# motor_control.net
KiCad netlist of a schematic drawn in Altium Designer
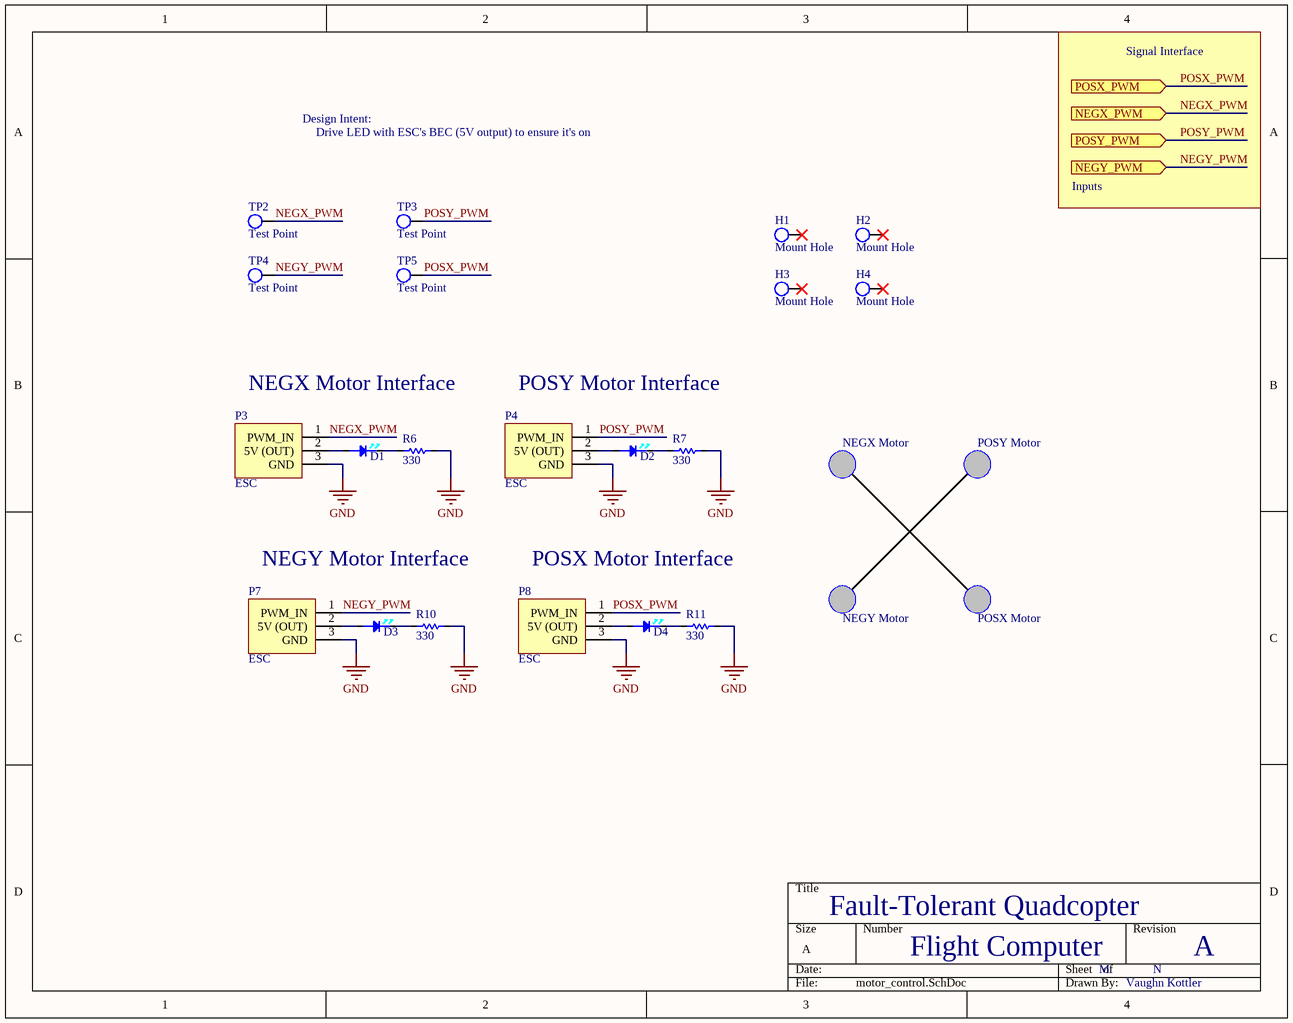
[diagram p0: motor_control.SchDoc]

(export (version "E")
  (design (tool "Eeschema 10.0.6"))
  (components
    (comp (ref "D1")
      (value "LED-WHT-20mA")
      (footprint "LED-0805")
      (description "2.2V, 0805")
      (libsource (lib "passive") (part "LED-WHT-20mA"))
    )
    (comp (ref "D2")
      (value "LED-WHT-20mA")
      (footprint "LED-0805")
      (description "2.2V, 0805")
      (libsource (lib "passive") (part "LED-WHT-20mA"))
    )
    (comp (ref "D3")
      (value "LED-WHT-20mA")
      (footprint "LED-0805")
      (description "2.2V, 0805")
      (libsource (lib "passive") (part "LED-WHT-20mA"))
    )
    (comp (ref "D4")
      (value "LED-WHT-20mA")
      (footprint "LED-0805")
      (description "2.2V, 0805")
      (libsource (lib "passive") (part "LED-WHT-20mA"))
    )
    (comp (ref "H1")
      (value "Mount Hole")
      (footprint "4mm Mount Hole")
      (libsource (lib "connector") (part "Mount Hole"))
    )
    (comp (ref "H2")
      (value "Mount Hole")
      (footprint "4mm Mount Hole")
      (libsource (lib "connector") (part "Mount Hole"))
    )
    (comp (ref "H3")
      (value "Mount Hole")
      (footprint "4mm Mount Hole")
      (libsource (lib "connector") (part "Mount Hole"))
    )
    (comp (ref "H4")
      (value "Mount Hole")
      (footprint "4mm Mount Hole")
      (libsource (lib "connector") (part "Mount Hole"))
    )
    (comp (ref "P3")
      (value "ESC")
      (footprint "ESC RA")
      (description "PWM Interface, 0.1\" Pitch 1x3")
      (libsource (lib "connector") (part "ESC"))
    )
    (comp (ref "P4")
      (value "ESC")
      (footprint "ESC RA")
      (description "PWM Interface, 0.1\" Pitch 1x3")
      (libsource (lib "connector") (part "ESC"))
    )
    (comp (ref "P7")
      (value "ESC")
      (footprint "ESC RA")
      (description "PWM Interface, 0.1\" Pitch 1x3")
      (libsource (lib "connector") (part "ESC"))
    )
    (comp (ref "P8")
      (value "ESC")
      (footprint "ESC RA")
      (description "PWM Interface, 0.1\" Pitch 1x3")
      (libsource (lib "connector") (part "ESC"))
    )
    (comp (ref "R6")
      (value "330")
      (footprint "RES-0805")
      (description "0805")
      (libsource (lib "passive") (part "RES-330-1/8W"))
    )
    (comp (ref "R7")
      (value "330")
      (footprint "RES-0805")
      (description "0805")
      (libsource (lib "passive") (part "RES-330-1/8W"))
    )
    (comp (ref "R10")
      (value "330")
      (footprint "RES-0805")
      (description "0805")
      (libsource (lib "passive") (part "RES-330-1/8W"))
    )
    (comp (ref "R11")
      (value "330")
      (footprint "RES-0805")
      (description "0805")
      (libsource (lib "passive") (part "RES-330-1/8W"))
    )
    (comp (ref "TP2")
      (value "Test Point")
      (footprint "0603 Test Point")
      (description "0603")
      (libsource (lib "passive") (part "Test Point"))
    )
    (comp (ref "TP3")
      (value "Test Point")
      (footprint "0603 Test Point")
      (description "0603")
      (libsource (lib "passive") (part "Test Point"))
    )
    (comp (ref "TP4")
      (value "Test Point")
      (footprint "0603 Test Point")
      (description "0603")
      (libsource (lib "passive") (part "Test Point"))
    )
    (comp (ref "TP5")
      (value "Test Point")
      (footprint "0603 Test Point")
      (description "0603")
      (libsource (lib "passive") (part "Test Point"))
    )
  )
  (nets
    (net (code "1") (name "/NEGX_PWM") (class "Default")
      (node (ref "P3") (pin "1") (pinfunction "PWM_IN_1") (pintype "passive"))
      (node (ref "TP2") (pin "1") (pinfunction "1_1") (pintype "passive"))
    )
    (net (code "2") (name "/NEGY_PWM") (class "Default")
      (node (ref "P7") (pin "1") (pinfunction "PWM_IN_1") (pintype "passive"))
      (node (ref "TP4") (pin "1") (pinfunction "1_1") (pintype "passive"))
    )
    (net (code "3") (name "/POSX_PWM") (class "Default")
      (node (ref "P8") (pin "1") (pinfunction "PWM_IN_1") (pintype "passive"))
      (node (ref "TP5") (pin "1") (pinfunction "1_1") (pintype "passive"))
    )
    (net (code "4") (name "/POSY_PWM") (class "Default")
      (node (ref "P4") (pin "1") (pinfunction "PWM_IN_1") (pintype "passive"))
      (node (ref "TP3") (pin "1") (pinfunction "1_1") (pintype "passive"))
    )
    (net (code "5") (name "GND") (class "Default")
      (node (ref "P3") (pin "3") (pinfunction "GND_3") (pintype "passive"))
      (node (ref "P4") (pin "3") (pinfunction "GND_3") (pintype "passive"))
      (node (ref "P7") (pin "3") (pinfunction "GND_3") (pintype "passive"))
      (node (ref "P8") (pin "3") (pinfunction "GND_3") (pintype "passive"))
      (node (ref "R10") (pin "2") (pinfunction "2_2") (pintype "passive"))
      (node (ref "R11") (pin "2") (pinfunction "2_2") (pintype "passive"))
      (node (ref "R6") (pin "2") (pinfunction "2_2") (pintype "passive"))
      (node (ref "R7") (pin "2") (pinfunction "2_2") (pintype "passive"))
    )
    (net (code "6") (name "Net-(D1-AN)") (class "Default")
      (node (ref "D1") (pin "2") (pinfunction "AN_2") (pintype "passive"))
      (node (ref "R6") (pin "1") (pinfunction "1_1") (pintype "passive"))
    )
    (net (code "7") (name "Net-(D1-CT)") (class "Default")
      (node (ref "D1") (pin "1") (pinfunction "CT_1") (pintype "passive"))
      (node (ref "P3") (pin "2") (pinfunction "5V_(OUT)_2") (pintype "passive"))
    )
    (net (code "8") (name "Net-(D2-AN)") (class "Default")
      (node (ref "D2") (pin "2") (pinfunction "AN_2") (pintype "passive"))
      (node (ref "R7") (pin "1") (pinfunction "1_1") (pintype "passive"))
    )
    (net (code "9") (name "Net-(D2-CT)") (class "Default")
      (node (ref "D2") (pin "1") (pinfunction "CT_1") (pintype "passive"))
      (node (ref "P4") (pin "2") (pinfunction "5V_(OUT)_2") (pintype "passive"))
    )
    (net (code "10") (name "Net-(D3-AN)") (class "Default")
      (node (ref "D3") (pin "2") (pinfunction "AN_2") (pintype "passive"))
      (node (ref "R10") (pin "1") (pinfunction "1_1") (pintype "passive"))
    )
    (net (code "11") (name "Net-(D3-CT)") (class "Default")
      (node (ref "D3") (pin "1") (pinfunction "CT_1") (pintype "passive"))
      (node (ref "P7") (pin "2") (pinfunction "5V_(OUT)_2") (pintype "passive"))
    )
    (net (code "12") (name "Net-(D4-AN)") (class "Default")
      (node (ref "D4") (pin "2") (pinfunction "AN_2") (pintype "passive"))
      (node (ref "R11") (pin "1") (pinfunction "1_1") (pintype "passive"))
    )
    (net (code "13") (name "Net-(D4-CT)") (class "Default")
      (node (ref "D4") (pin "1") (pinfunction "CT_1") (pintype "passive"))
      (node (ref "P8") (pin "2") (pinfunction "5V_(OUT)_2") (pintype "passive"))
    )
    (net (code "14") (name "unconnected-(H1-PadH)") (class "Default")
      (node (ref "H1") (pin "H") (pinfunction "H_H") (pintype "passive+no_connect"))
    )
    (net (code "15") (name "unconnected-(H2-PadH)") (class "Default")
      (node (ref "H2") (pin "H") (pinfunction "H_H") (pintype "passive+no_connect"))
    )
    (net (code "16") (name "unconnected-(H3-PadH)") (class "Default")
      (node (ref "H3") (pin "H") (pinfunction "H_H") (pintype "passive+no_connect"))
    )
    (net (code "17") (name "unconnected-(H4-PadH)") (class "Default")
      (node (ref "H4") (pin "H") (pinfunction "H_H") (pintype "passive+no_connect"))
    )
  )
)
